# CAN_node.net
KiCad netlist of a schematic drawn in EAGLE
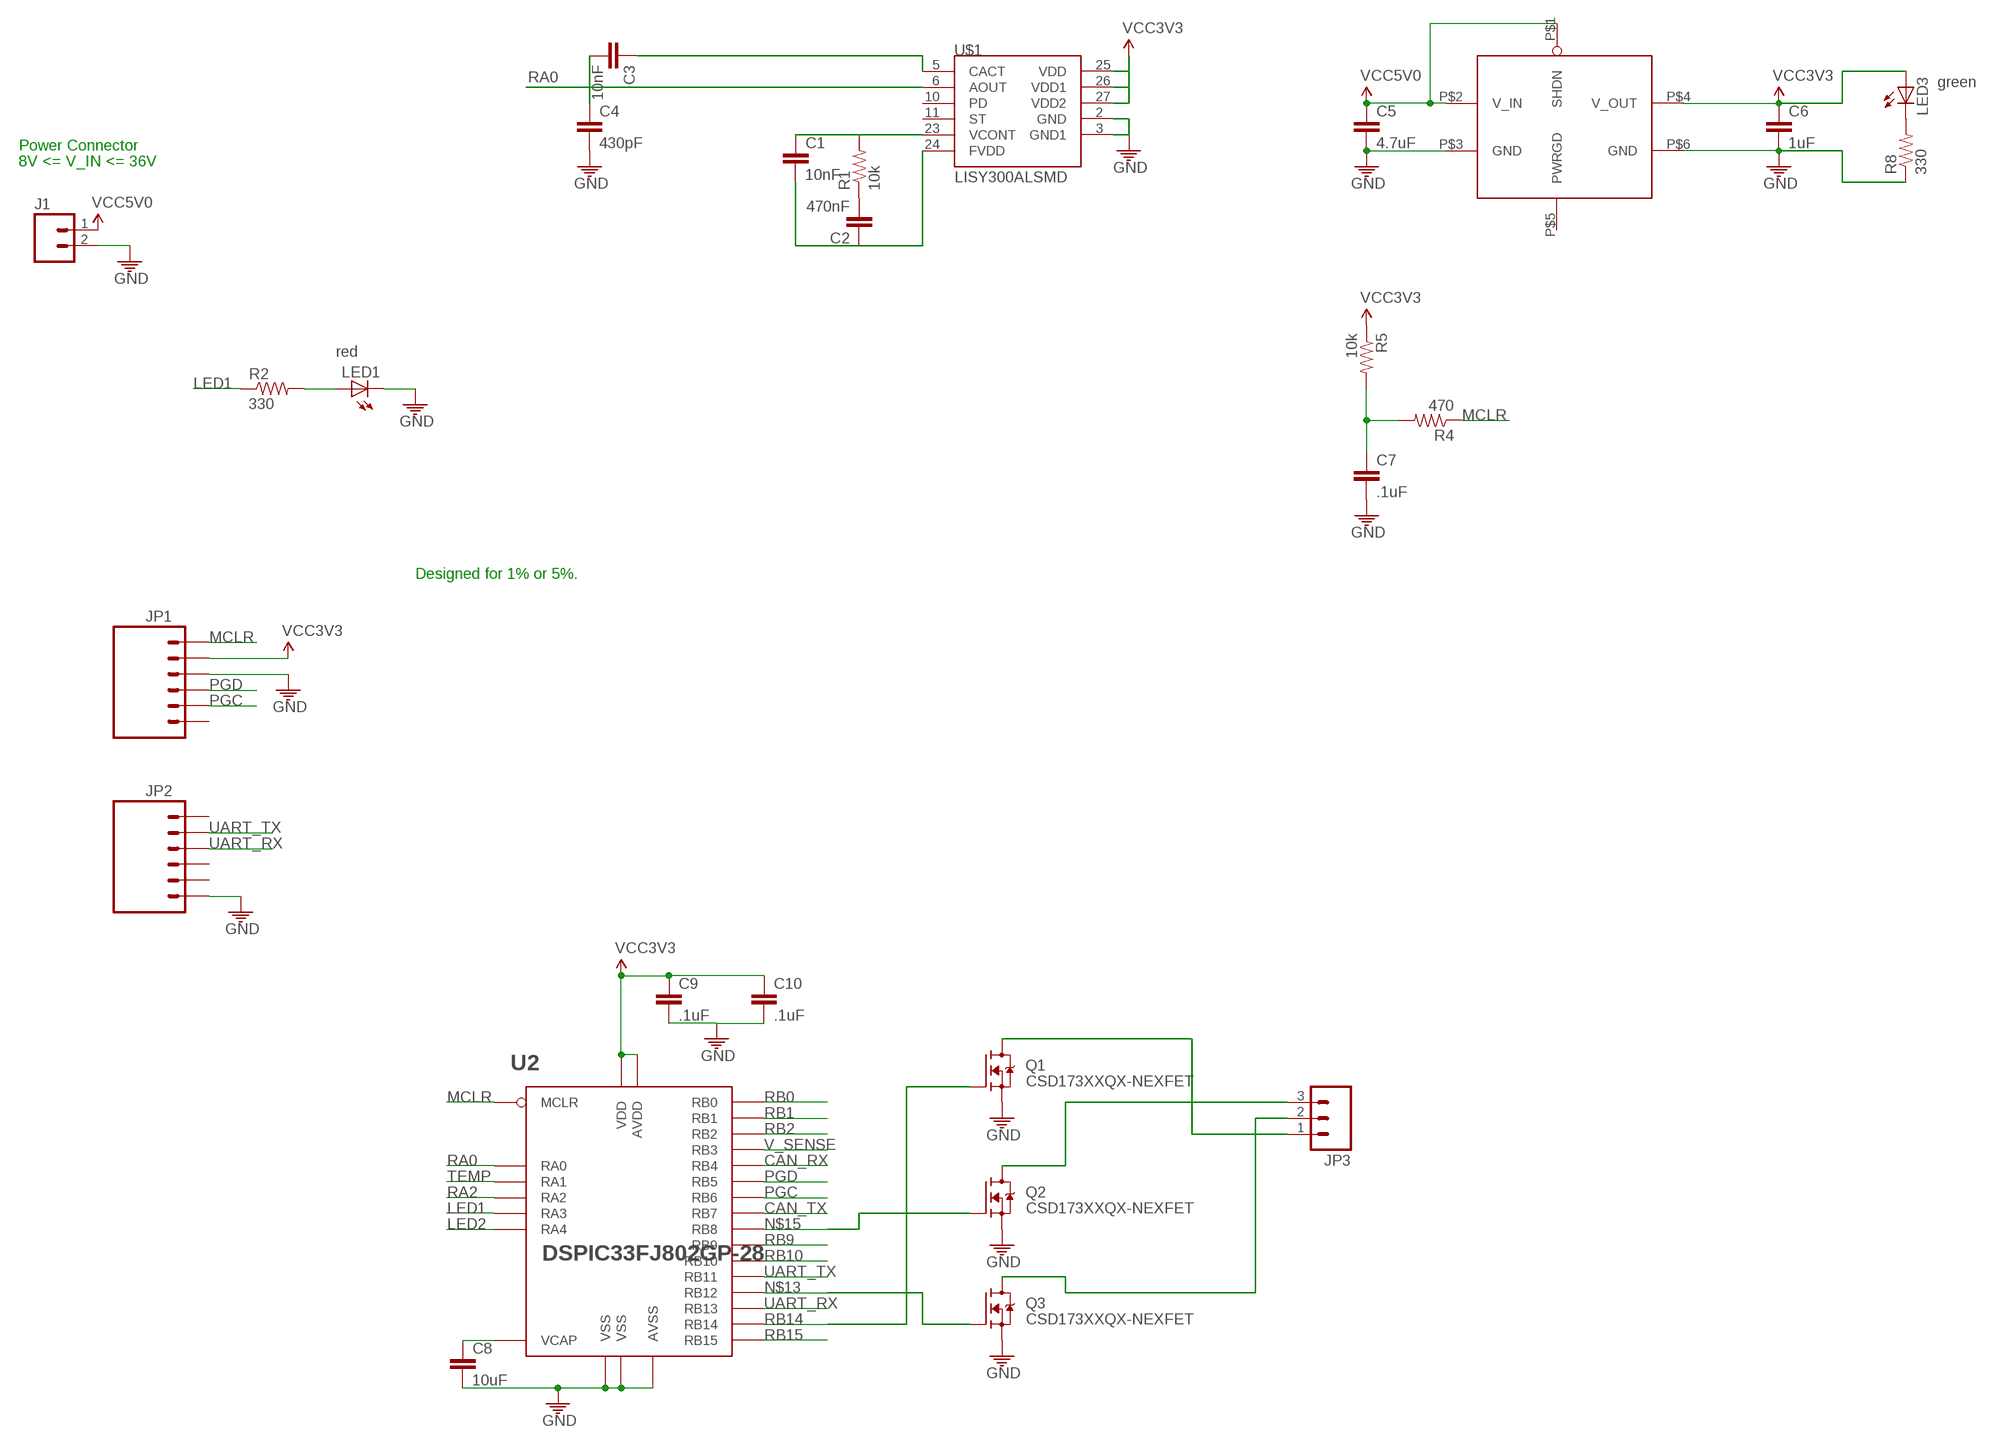
[diagram p0: schematic, sheet 1]

(export (version "E")
  (design (tool "Eeschema 10.0.6"))
  (components
    (comp (ref "C1")
      (value "10nF")
      (footprint "eagle-import:1206")
      (libsource (lib "eagle-import") (part "CAP1206"))
    )
    (comp (ref "C2")
      (value "470nF")
      (footprint "eagle-import:1206")
      (libsource (lib "eagle-import") (part "CAP1206"))
    )
    (comp (ref "C3")
      (value "10nF")
      (footprint "eagle-import:1206")
      (libsource (lib "eagle-import") (part "CAP1206"))
    )
    (comp (ref "C4")
      (value "430pF")
      (footprint "eagle-import:1206")
      (libsource (lib "eagle-import") (part "CAP1206"))
    )
    (comp (ref "C5")
      (value "4.7uF")
      (footprint "eagle-import:1206")
      (libsource (lib "eagle-import") (part "CMPE118lib_CAP1206"))
    )
    (comp (ref "C6")
      (value "1uF")
      (footprint "eagle-import:1206")
      (libsource (lib "eagle-import") (part "CMPE118lib_CAP1206"))
    )
    (comp (ref "C7")
      (value ".1uF")
      (footprint "eagle-import:1206")
      (libsource (lib "eagle-import") (part "CMPE118lib_CAP1206"))
    )
    (comp (ref "C8")
      (value "10uF")
      (footprint "eagle-import:1206")
      (libsource (lib "eagle-import") (part "CMPE118lib_CAP1206"))
    )
    (comp (ref "C9")
      (value ".1uF")
      (footprint "eagle-import:1206")
      (libsource (lib "eagle-import") (part "CMPE118lib_CAP1206"))
    )
    (comp (ref "C10")
      (value ".1uF")
      (footprint "eagle-import:1206")
      (libsource (lib "eagle-import") (part "CMPE118lib_CAP1206"))
    )
    (comp (ref "J1")
      (value "M02PTH")
      (footprint "eagle-import:1X02")
      (libsource (lib "eagle-import") (part "M02PTH"))
    )
    (comp (ref "JP1")
      (value "M06LOCK")
      (footprint "eagle-import:1X06_LOCK")
      (libsource (lib "eagle-import") (part "M06LOCK"))
    )
    (comp (ref "JP2")
      (value "M06LOCK")
      (footprint "eagle-import:1X06_LOCK")
      (libsource (lib "eagle-import") (part "M06LOCK"))
    )
    (comp (ref "JP3")
      (value "M03PTH")
      (footprint "eagle-import:1X03")
      (libsource (lib "eagle-import") (part "M03PTH"))
    )
    (comp (ref "LED1")
      (value "LED1206")
      (footprint "eagle-import:LED-1206")
      (fields (field (name "COLOR") "red"))
      (libsource (lib "eagle-import") (part "LED1206"))
    )
    (comp (ref "LED3")
      (value "LED1206")
      (footprint "eagle-import:LED-1206")
      (fields (field (name "COLOR") "green"))
      (libsource (lib "eagle-import") (part "LED1206"))
    )
    (comp (ref "Q1")
      (value "CSD173XXQX-NEXFET")
      (footprint "eagle-import:CSD173XXQX")
      (libsource (lib "eagle-import") (part "CSD173XXQX-NEXFET"))
    )
    (comp (ref "Q2")
      (value "CSD173XXQX-NEXFET")
      (footprint "eagle-import:CSD173XXQX")
      (libsource (lib "eagle-import") (part "CSD173XXQX-NEXFET"))
    )
    (comp (ref "Q3")
      (value "CSD173XXQX-NEXFET")
      (footprint "eagle-import:CSD173XXQX")
      (libsource (lib "eagle-import") (part "CSD173XXQX-NEXFET"))
    )
    (comp (ref "R1")
      (value "10k")
      (footprint "eagle-import:0805")
      (libsource (lib "eagle-import") (part "RESISTOR0805-RES"))
    )
    (comp (ref "R2")
      (value "330")
      (footprint "eagle-import:0805")
      (libsource (lib "eagle-import") (part "CMPE118lib_RESISTOR0805-RES"))
    )
    (comp (ref "R4")
      (value "470")
      (footprint "eagle-import:0805")
      (libsource (lib "eagle-import") (part "CMPE118lib_RESISTOR0805-RES"))
    )
    (comp (ref "R5")
      (value "10k")
      (footprint "eagle-import:0805")
      (libsource (lib "eagle-import") (part "CMPE118lib_RESISTOR0805-RES"))
    )
    (comp (ref "R8")
      (value "330")
      (footprint "eagle-import:0805")
      (libsource (lib "eagle-import") (part "CMPE118lib_RESISTOR0805-RES"))
    )
    (comp (ref "U$1")
      (value "LISY300ALSMD")
      (footprint "eagle-import:LGA28")
      (libsource (lib "eagle-import") (part "LISY300ALSMD"))
    )
    (comp (ref "U2")
      (value "DSPIC33FJ802GP-28")
      (footprint "eagle-import:SOIC28-W")
      (libsource (lib "eagle-import") (part "DSPIC33FJ802GP-28"))
    )
    (comp (ref "U3")
      (value "MCP1826")
      (footprint "eagle-import:SOT223-5")
      (libsource (lib "eagle-import") (part "MCP1826"))
    )
  )
  (nets
    (net (code "1") (name "/CAN_RX") (class "Default")
      (node (ref "U2") (pin "P$11") (pinfunction "RB4_P$11") (pintype "bidirectional"))
    )
    (net (code "2") (name "/CAN_TX") (class "Default")
      (node (ref "U2") (pin "P$16") (pinfunction "RB7_P$16") (pintype "bidirectional"))
    )
    (net (code "3") (name "/LED1") (class "Default")
      (node (ref "R2") (pin "1") (pinfunction "1_1") (pintype "passive"))
      (node (ref "U2") (pin "P$10") (pinfunction "RA3_P$10") (pintype "bidirectional"))
    )
    (net (code "4") (name "/LED2") (class "Default")
      (node (ref "U2") (pin "P$12") (pinfunction "RA4_P$12") (pintype "bidirectional"))
    )
    (net (code "5") (name "/MCLR") (class "Default")
      (node (ref "JP1") (pin "1") (pinfunction "1_1") (pintype "passive"))
      (node (ref "R4") (pin "1") (pinfunction "1_1") (pintype "passive"))
      (node (ref "U2") (pin "P$1") (pinfunction "MCLR_P$1") (pintype "bidirectional"))
    )
    (net (code "6") (name "/N$13") (class "Default")
      (node (ref "Q3") (pin "G") (pinfunction "G_G") (pintype "passive"))
      (node (ref "U2") (pin "P$23") (pinfunction "RB12_P$23") (pintype "bidirectional"))
    )
    (net (code "7") (name "/N$15") (class "Default")
      (node (ref "Q2") (pin "G") (pinfunction "G_G") (pintype "passive"))
      (node (ref "U2") (pin "P$17") (pinfunction "RB8_P$17") (pintype "bidirectional"))
    )
    (net (code "8") (name "/PGC") (class "Default")
      (node (ref "JP1") (pin "5") (pinfunction "5_5") (pintype "passive"))
      (node (ref "U2") (pin "P$15") (pinfunction "RB6_P$15") (pintype "bidirectional"))
    )
    (net (code "9") (name "/PGD") (class "Default")
      (node (ref "JP1") (pin "4") (pinfunction "4_4") (pintype "passive"))
      (node (ref "U2") (pin "P$14") (pinfunction "RB5_P$14") (pintype "bidirectional"))
    )
    (net (code "10") (name "/RA0") (class "Default")
      (node (ref "C3") (pin "2") (pinfunction "2_2") (pintype "passive"))
      (node (ref "C4") (pin "1") (pinfunction "1_1") (pintype "passive"))
      (node (ref "U$1") (pin "6") (pinfunction "AOUT_6") (pintype "bidirectional"))
      (node (ref "U2") (pin "P$2") (pinfunction "RA0_P$2") (pintype "bidirectional"))
    )
    (net (code "11") (name "/RA2") (class "Default")
      (node (ref "U2") (pin "P$9") (pinfunction "RA2_P$9") (pintype "bidirectional"))
    )
    (net (code "12") (name "/RB0") (class "Default")
      (node (ref "U2") (pin "P$4") (pinfunction "RB0_P$4") (pintype "bidirectional"))
    )
    (net (code "13") (name "/RB1") (class "Default")
      (node (ref "U2") (pin "P$5") (pinfunction "RB1_P$5") (pintype "bidirectional"))
    )
    (net (code "14") (name "/RB2") (class "Default")
      (node (ref "U2") (pin "P$6") (pinfunction "RB2_P$6") (pintype "bidirectional"))
    )
    (net (code "15") (name "/RB9") (class "Default")
      (node (ref "U2") (pin "P$18") (pinfunction "RB9_P$18") (pintype "bidirectional"))
    )
    (net (code "16") (name "/RB10") (class "Default")
      (node (ref "U2") (pin "P$22") (pinfunction "RB10_P$22") (pintype "bidirectional"))
    )
    (net (code "17") (name "/RB14") (class "Default")
      (node (ref "Q1") (pin "G") (pinfunction "G_G") (pintype "passive"))
      (node (ref "U2") (pin "P$25") (pinfunction "RB14_P$25") (pintype "bidirectional"))
    )
    (net (code "18") (name "/RB15") (class "Default")
      (node (ref "U2") (pin "P$26") (pinfunction "RB15_P$26") (pintype "bidirectional"))
    )
    (net (code "19") (name "/TEMP") (class "Default")
      (node (ref "U2") (pin "P$3") (pinfunction "RA1_P$3") (pintype "bidirectional"))
    )
    (net (code "20") (name "/UART_RX") (class "Default")
      (node (ref "JP2") (pin "3") (pinfunction "3_3") (pintype "passive"))
      (node (ref "U2") (pin "P$24") (pinfunction "RB13_P$24") (pintype "bidirectional"))
    )
    (net (code "21") (name "/UART_TX") (class "Default")
      (node (ref "JP2") (pin "2") (pinfunction "2_2") (pintype "passive"))
      (node (ref "U2") (pin "P$21") (pinfunction "RB11_P$21") (pintype "bidirectional"))
    )
    (net (code "22") (name "/V_SENSE") (class "Default")
      (node (ref "U2") (pin "P$7") (pinfunction "RB3_P$7") (pintype "bidirectional"))
    )
    (net (code "23") (name "GND") (class "Default")
      (node (ref "C10") (pin "2") (pinfunction "2_2") (pintype "passive"))
      (node (ref "C4") (pin "2") (pinfunction "2_2") (pintype "passive"))
      (node (ref "C5") (pin "2") (pinfunction "2_2") (pintype "passive"))
      (node (ref "C6") (pin "2") (pinfunction "2_2") (pintype "passive"))
      (node (ref "C7") (pin "2") (pinfunction "2_2") (pintype "passive"))
      (node (ref "C8") (pin "2") (pinfunction "2_2") (pintype "passive"))
      (node (ref "C9") (pin "2") (pinfunction "2_2") (pintype "passive"))
      (node (ref "J1") (pin "2") (pinfunction "1_2") (pintype "passive"))
      (node (ref "JP1") (pin "3") (pinfunction "3_3") (pintype "passive"))
      (node (ref "JP2") (pin "6") (pinfunction "6_6") (pintype "passive"))
      (node (ref "LED1") (pin "C") (pinfunction "C_C") (pintype "passive"))
      (node (ref "Q1") (pin "S1") (pinfunction "S_S1") (pintype "passive"))
      (node (ref "Q1") (pin "S2") (pinfunction "S_S2") (pintype "passive"))
      (node (ref "Q1") (pin "S3") (pinfunction "S_S3") (pintype "passive"))
      (node (ref "Q2") (pin "S1") (pinfunction "S_S1") (pintype "passive"))
      (node (ref "Q2") (pin "S2") (pinfunction "S_S2") (pintype "passive"))
      (node (ref "Q2") (pin "S3") (pinfunction "S_S3") (pintype "passive"))
      (node (ref "Q3") (pin "S1") (pinfunction "S_S1") (pintype "passive"))
      (node (ref "Q3") (pin "S2") (pinfunction "S_S2") (pintype "passive"))
      (node (ref "Q3") (pin "S3") (pinfunction "S_S3") (pintype "passive"))
      (node (ref "R8") (pin "1") (pinfunction "1_1") (pintype "passive"))
      (node (ref "U$1") (pin "2") (pinfunction "GND_2") (pintype "bidirectional"))
      (node (ref "U$1") (pin "3") (pinfunction "GND1_3") (pintype "bidirectional"))
      (node (ref "U2") (pin "P$19") (pinfunction "VSS_P$19") (pintype "power_in"))
      (node (ref "U2") (pin "P$27") (pinfunction "AVSS_P$27") (pintype "input"))
      (node (ref "U2") (pin "P$8") (pinfunction "VSS_P$8") (pintype "power_in"))
      (node (ref "U3") (pin "P$3") (pinfunction "GND_P$3") (pintype "power_in"))
      (node (ref "U3") (pin "P$6") (pinfunction "GND_P$6") (pintype "power_in"))
    )
    (net (code "24") (name "Net-(C2-Pad2)") (class "Default")
      (node (ref "C2") (pin "2") (pinfunction "2_2") (pintype "passive"))
      (node (ref "R1") (pin "1") (pinfunction "1_1") (pintype "passive"))
    )
    (net (code "25") (name "Net-(C7-Pad1)") (class "Default")
      (node (ref "C7") (pin "1") (pinfunction "1_1") (pintype "passive"))
      (node (ref "R4") (pin "2") (pinfunction "2_2") (pintype "passive"))
      (node (ref "R5") (pin "2") (pinfunction "2_2") (pintype "passive"))
    )
    (net (code "26") (name "Net-(JP3-Pad1)") (class "Default")
      (node (ref "JP3") (pin "1") (pinfunction "1_1") (pintype "passive"))
      (node (ref "Q1") (pin "D") (pinfunction "D_D") (pintype "passive"))
    )
    (net (code "27") (name "Net-(JP3-Pad2)") (class "Default")
      (node (ref "JP3") (pin "2") (pinfunction "2_2") (pintype "passive"))
      (node (ref "Q3") (pin "D") (pinfunction "D_D") (pintype "passive"))
    )
    (net (code "28") (name "Net-(JP3-Pad3)") (class "Default")
      (node (ref "JP3") (pin "3") (pinfunction "3_3") (pintype "passive"))
      (node (ref "Q2") (pin "D") (pinfunction "D_D") (pintype "passive"))
    )
    (net (code "29") (name "Net-(LED1-PadA)") (class "Default")
      (node (ref "LED1") (pin "A") (pinfunction "A_A") (pintype "passive"))
      (node (ref "R2") (pin "2") (pinfunction "2_2") (pintype "passive"))
    )
    (net (code "30") (name "Net-(LED3-PadC)") (class "Default")
      (node (ref "LED3") (pin "C") (pinfunction "C_C") (pintype "passive"))
      (node (ref "R8") (pin "2") (pinfunction "2_2") (pintype "passive"))
    )
    (net (code "31") (name "Net-(U$1-CACT)") (class "Default")
      (node (ref "C3") (pin "1") (pinfunction "1_1") (pintype "passive"))
      (node (ref "U$1") (pin "5") (pinfunction "CACT_5") (pintype "bidirectional"))
    )
    (net (code "32") (name "Net-(U$1-FVDD)") (class "Default")
      (node (ref "C1") (pin "2") (pinfunction "2_2") (pintype "passive"))
      (node (ref "C2") (pin "1") (pinfunction "1_1") (pintype "passive"))
      (node (ref "U$1") (pin "24") (pinfunction "FVDD_24") (pintype "bidirectional"))
    )
    (net (code "33") (name "Net-(U$1-VCONT)") (class "Default")
      (node (ref "C1") (pin "1") (pinfunction "1_1") (pintype "passive"))
      (node (ref "R1") (pin "2") (pinfunction "2_2") (pintype "passive"))
      (node (ref "U$1") (pin "23") (pinfunction "VCONT_23") (pintype "bidirectional"))
    )
    (net (code "34") (name "Net-(U2-VCAP)") (class "Default")
      (node (ref "C8") (pin "1") (pinfunction "1_1") (pintype "passive"))
      (node (ref "U2") (pin "P$20") (pinfunction "VCAP_P$20") (pintype "input"))
    )
    (net (code "35") (name "VCC3V3") (class "Default")
      (node (ref "C10") (pin "1") (pinfunction "1_1") (pintype "passive"))
      (node (ref "C6") (pin "1") (pinfunction "1_1") (pintype "passive"))
      (node (ref "C9") (pin "1") (pinfunction "1_1") (pintype "passive"))
      (node (ref "JP1") (pin "2") (pinfunction "2_2") (pintype "passive"))
      (node (ref "LED3") (pin "A") (pinfunction "A_A") (pintype "passive"))
      (node (ref "R5") (pin "1") (pinfunction "1_1") (pintype "passive"))
      (node (ref "U$1") (pin "25") (pinfunction "VDD_25") (pintype "bidirectional"))
      (node (ref "U$1") (pin "26") (pinfunction "VDD1_26") (pintype "bidirectional"))
      (node (ref "U$1") (pin "27") (pinfunction "VDD2_27") (pintype "bidirectional"))
      (node (ref "U2") (pin "P$13") (pinfunction "VDD_P$13") (pintype "power_in"))
      (node (ref "U2") (pin "P$28") (pinfunction "AVDD_P$28") (pintype "input"))
      (node (ref "U3") (pin "P$4") (pinfunction "V_OUT_P$4") (pintype "output"))
    )
    (net (code "36") (name "VCC5V0") (class "Default")
      (node (ref "C5") (pin "1") (pinfunction "1_1") (pintype "passive"))
      (node (ref "J1") (pin "1") (pinfunction "2_1") (pintype "passive"))
      (node (ref "U3") (pin "P$1") (pinfunction "SHDN_P$1") (pintype "input"))
      (node (ref "U3") (pin "P$2") (pinfunction "V_IN_P$2") (pintype "power_in"))
    )
    (net (code "37") (name "unconnected-(JP1-Pad6)") (class "Default")
      (node (ref "JP1") (pin "6") (pinfunction "6_6") (pintype "passive"))
    )
    (net (code "38") (name "unconnected-(JP2-Pad1)") (class "Default")
      (node (ref "JP2") (pin "1") (pinfunction "1_1") (pintype "passive"))
    )
    (net (code "39") (name "unconnected-(JP2-Pad4)") (class "Default")
      (node (ref "JP2") (pin "4") (pinfunction "4_4") (pintype "passive"))
    )
    (net (code "40") (name "unconnected-(JP2-Pad5)") (class "Default")
      (node (ref "JP2") (pin "5") (pinfunction "5_5") (pintype "passive"))
    )
    (net (code "41") (name "unconnected-(U$1-PD-Pad10)") (class "Default")
      (node (ref "U$1") (pin "10") (pinfunction "PD_10") (pintype "bidirectional"))
    )
    (net (code "42") (name "unconnected-(U$1-ST-Pad11)") (class "Default")
      (node (ref "U$1") (pin "11") (pinfunction "ST_11") (pintype "bidirectional"))
    )
    (net (code "43") (name "unconnected-(U3-PWRGD-PadP$5)") (class "Default")
      (node (ref "U3") (pin "P$5") (pinfunction "PWRGD_P$5") (pintype "open_collector"))
    )
  )
)
